# lasers.net
KiCad netlist of a schematic drawn in Altium Designer
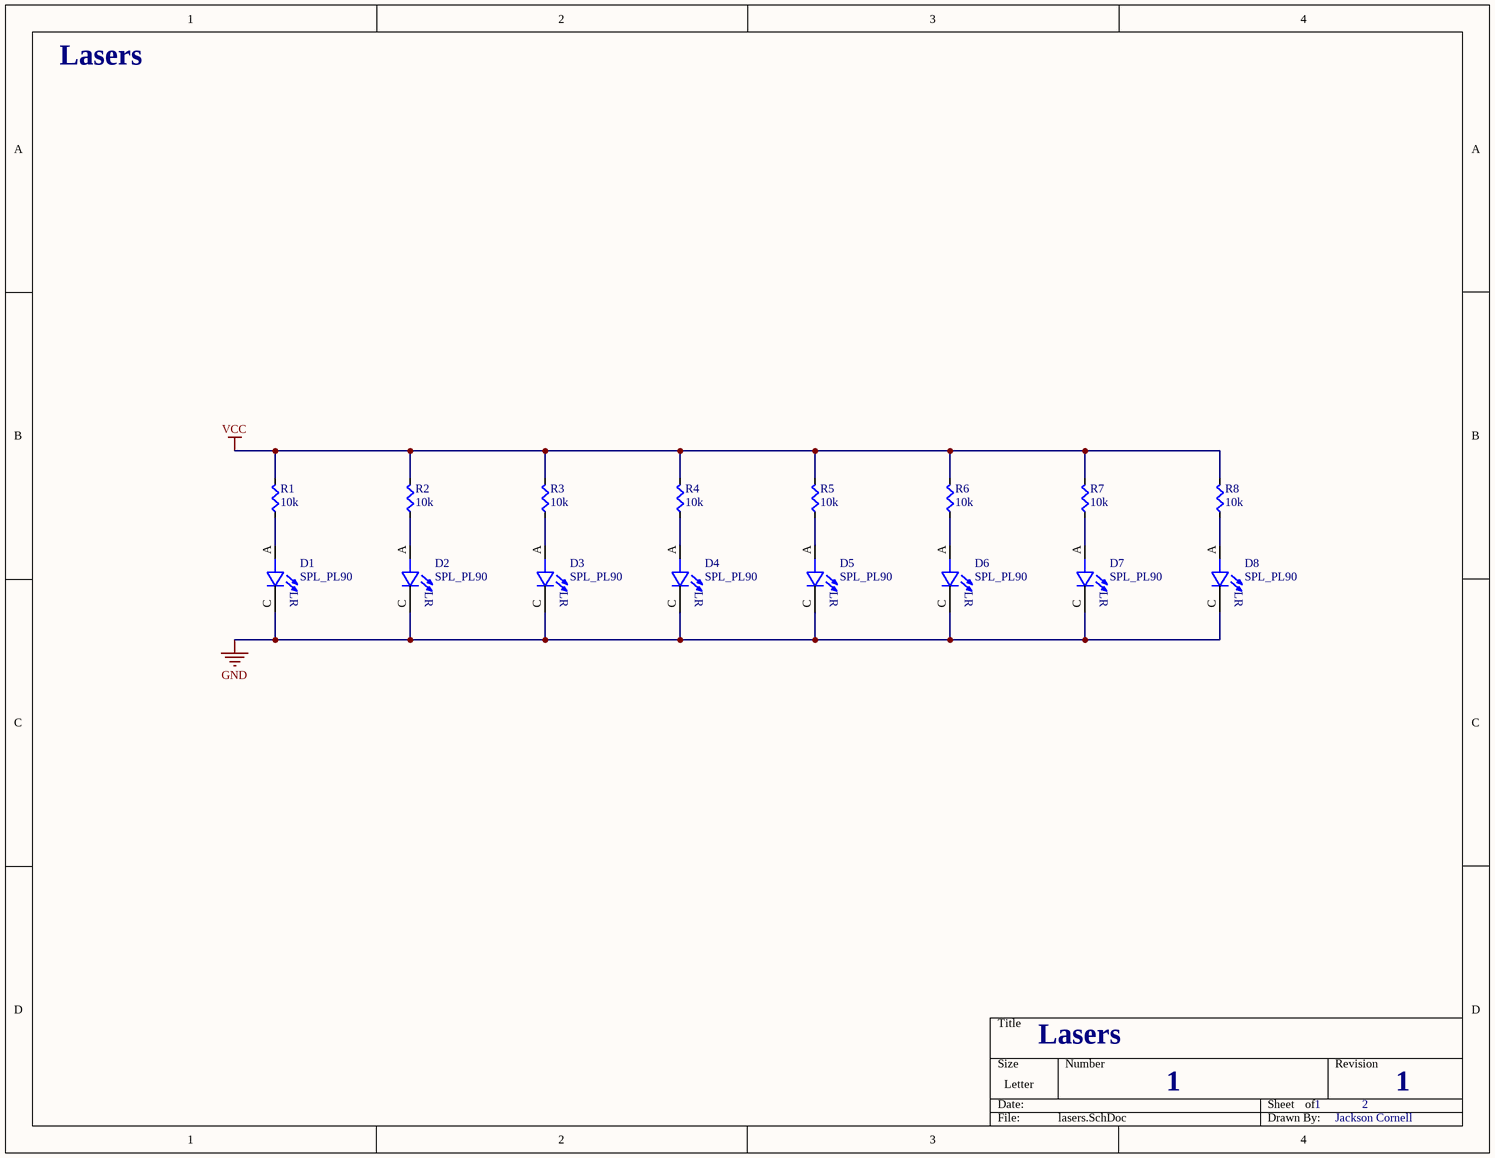
[diagram p0: lasers.SchDoc]

(export (version "E")
  (design (tool "Eeschema 10.0.6"))
  (components
    (comp (ref "D1")
      (value "SPL_PL90")
      (footprint "LEDRD254W40D590H700")
      (description "Laser Diode 905nm 90W 8 ~ 11V 40A Radial, Can _5.7mm_")
      (fields (field (name "MP") "SPL PL90") (field (name "MF") "OSRAM Opto"))
      (libsource (lib "SPL_PL90") (part "SPL_PL90"))
    )
    (comp (ref "D2")
      (value "SPL_PL90")
      (footprint "LEDRD254W40D590H700")
      (description "Laser Diode 905nm 90W 8 ~ 11V 40A Radial, Can _5.7mm_")
      (fields (field (name "MP") "SPL PL90") (field (name "MF") "OSRAM Opto"))
      (libsource (lib "SPL_PL90") (part "SPL_PL90"))
    )
    (comp (ref "D3")
      (value "SPL_PL90")
      (footprint "LEDRD254W40D590H700")
      (description "Laser Diode 905nm 90W 8 ~ 11V 40A Radial, Can _5.7mm_")
      (fields (field (name "MP") "SPL PL90") (field (name "MF") "OSRAM Opto"))
      (libsource (lib "SPL_PL90") (part "SPL_PL90"))
    )
    (comp (ref "D4")
      (value "SPL_PL90")
      (footprint "LEDRD254W40D590H700")
      (description "Laser Diode 905nm 90W 8 ~ 11V 40A Radial, Can _5.7mm_")
      (fields (field (name "MP") "SPL PL90") (field (name "MF") "OSRAM Opto"))
      (libsource (lib "SPL_PL90") (part "SPL_PL90"))
    )
    (comp (ref "D5")
      (value "SPL_PL90")
      (footprint "LEDRD254W40D590H700")
      (description "Laser Diode 905nm 90W 8 ~ 11V 40A Radial, Can _5.7mm_")
      (fields (field (name "MP") "SPL PL90") (field (name "MF") "OSRAM Opto"))
      (libsource (lib "SPL_PL90") (part "SPL_PL90"))
    )
    (comp (ref "D6")
      (value "SPL_PL90")
      (footprint "LEDRD254W40D590H700")
      (description "Laser Diode 905nm 90W 8 ~ 11V 40A Radial, Can _5.7mm_")
      (fields (field (name "MP") "SPL PL90") (field (name "MF") "OSRAM Opto"))
      (libsource (lib "SPL_PL90") (part "SPL_PL90"))
    )
    (comp (ref "D7")
      (value "SPL_PL90")
      (footprint "LEDRD254W40D590H700")
      (description "Laser Diode 905nm 90W 8 ~ 11V 40A Radial, Can _5.7mm_")
      (fields (field (name "MP") "SPL PL90") (field (name "MF") "OSRAM Opto"))
      (libsource (lib "SPL_PL90") (part "SPL_PL90"))
    )
    (comp (ref "D8")
      (value "SPL_PL90")
      (footprint "LEDRD254W40D590H700")
      (description "Laser Diode 905nm 90W 8 ~ 11V 40A Radial, Can _5.7mm_")
      (fields (field (name "MP") "SPL PL90") (field (name "MF") "OSRAM Opto"))
      (libsource (lib "SPL_PL90") (part "SPL_PL90"))
    )
    (comp (ref "R1")
      (value "10k")
      (footprint "RES0603")
      (fields (field (name "Comment") "Res"))
      (libsource (lib "Passives") (part "Res"))
    )
    (comp (ref "R2")
      (value "10k")
      (footprint "RES0603")
      (fields (field (name "Comment") "Res"))
      (libsource (lib "Passives") (part "Res"))
    )
    (comp (ref "R3")
      (value "10k")
      (footprint "RES0603")
      (fields (field (name "Comment") "Res"))
      (libsource (lib "Passives") (part "Res"))
    )
    (comp (ref "R4")
      (value "10k")
      (footprint "RES0603")
      (fields (field (name "Comment") "Res"))
      (libsource (lib "Passives") (part "Res"))
    )
    (comp (ref "R5")
      (value "10k")
      (footprint "RES0603")
      (fields (field (name "Comment") "Res"))
      (libsource (lib "Passives") (part "Res"))
    )
    (comp (ref "R6")
      (value "10k")
      (footprint "RES0603")
      (fields (field (name "Comment") "Res"))
      (libsource (lib "Passives") (part "Res"))
    )
    (comp (ref "R7")
      (value "10k")
      (footprint "RES0603")
      (fields (field (name "Comment") "Res"))
      (libsource (lib "Passives") (part "Res"))
    )
    (comp (ref "R8")
      (value "10k")
      (footprint "RES0603")
      (fields (field (name "Comment") "Res"))
      (libsource (lib "Passives") (part "Res"))
    )
  )
  (nets
    (net (code "1") (name "GND") (class "Default")
      (node (ref "D1") (pin "C") (pinfunction "C_C") (pintype "passive"))
      (node (ref "D2") (pin "C") (pinfunction "C_C") (pintype "passive"))
      (node (ref "D3") (pin "C") (pinfunction "C_C") (pintype "passive"))
      (node (ref "D4") (pin "C") (pinfunction "C_C") (pintype "passive"))
      (node (ref "D5") (pin "C") (pinfunction "C_C") (pintype "passive"))
      (node (ref "D6") (pin "C") (pinfunction "C_C") (pintype "passive"))
      (node (ref "D7") (pin "C") (pinfunction "C_C") (pintype "passive"))
      (node (ref "D8") (pin "C") (pinfunction "C_C") (pintype "passive"))
    )
    (net (code "2") (name "Net-(R1-B)") (class "Default")
      (node (ref "D1") (pin "A") (pinfunction "A_A") (pintype "passive"))
      (node (ref "R1") (pin "2") (pinfunction "B_2") (pintype "passive"))
    )
    (net (code "3") (name "Net-(R2-B)") (class "Default")
      (node (ref "D2") (pin "A") (pinfunction "A_A") (pintype "passive"))
      (node (ref "R2") (pin "2") (pinfunction "B_2") (pintype "passive"))
    )
    (net (code "4") (name "Net-(R3-B)") (class "Default")
      (node (ref "D3") (pin "A") (pinfunction "A_A") (pintype "passive"))
      (node (ref "R3") (pin "2") (pinfunction "B_2") (pintype "passive"))
    )
    (net (code "5") (name "Net-(R4-B)") (class "Default")
      (node (ref "D4") (pin "A") (pinfunction "A_A") (pintype "passive"))
      (node (ref "R4") (pin "2") (pinfunction "B_2") (pintype "passive"))
    )
    (net (code "6") (name "Net-(R5-B)") (class "Default")
      (node (ref "D5") (pin "A") (pinfunction "A_A") (pintype "passive"))
      (node (ref "R5") (pin "2") (pinfunction "B_2") (pintype "passive"))
    )
    (net (code "7") (name "Net-(R6-B)") (class "Default")
      (node (ref "D6") (pin "A") (pinfunction "A_A") (pintype "passive"))
      (node (ref "R6") (pin "2") (pinfunction "B_2") (pintype "passive"))
    )
    (net (code "8") (name "Net-(R7-B)") (class "Default")
      (node (ref "D7") (pin "A") (pinfunction "A_A") (pintype "passive"))
      (node (ref "R7") (pin "2") (pinfunction "B_2") (pintype "passive"))
    )
    (net (code "9") (name "Net-(R8-B)") (class "Default")
      (node (ref "D8") (pin "A") (pinfunction "A_A") (pintype "passive"))
      (node (ref "R8") (pin "2") (pinfunction "B_2") (pintype "passive"))
    )
    (net (code "10") (name "VCC") (class "Default")
      (node (ref "R1") (pin "1") (pinfunction "A_1") (pintype "passive"))
      (node (ref "R2") (pin "1") (pinfunction "A_1") (pintype "passive"))
      (node (ref "R3") (pin "1") (pinfunction "A_1") (pintype "passive"))
      (node (ref "R4") (pin "1") (pinfunction "A_1") (pintype "passive"))
      (node (ref "R5") (pin "1") (pinfunction "A_1") (pintype "passive"))
      (node (ref "R6") (pin "1") (pinfunction "A_1") (pintype "passive"))
      (node (ref "R7") (pin "1") (pinfunction "A_1") (pintype "passive"))
      (node (ref "R8") (pin "1") (pinfunction "A_1") (pintype "passive"))
    )
  )
)
